# 1_Motor.net
KiCad netlist of a schematic drawn in EAGLE
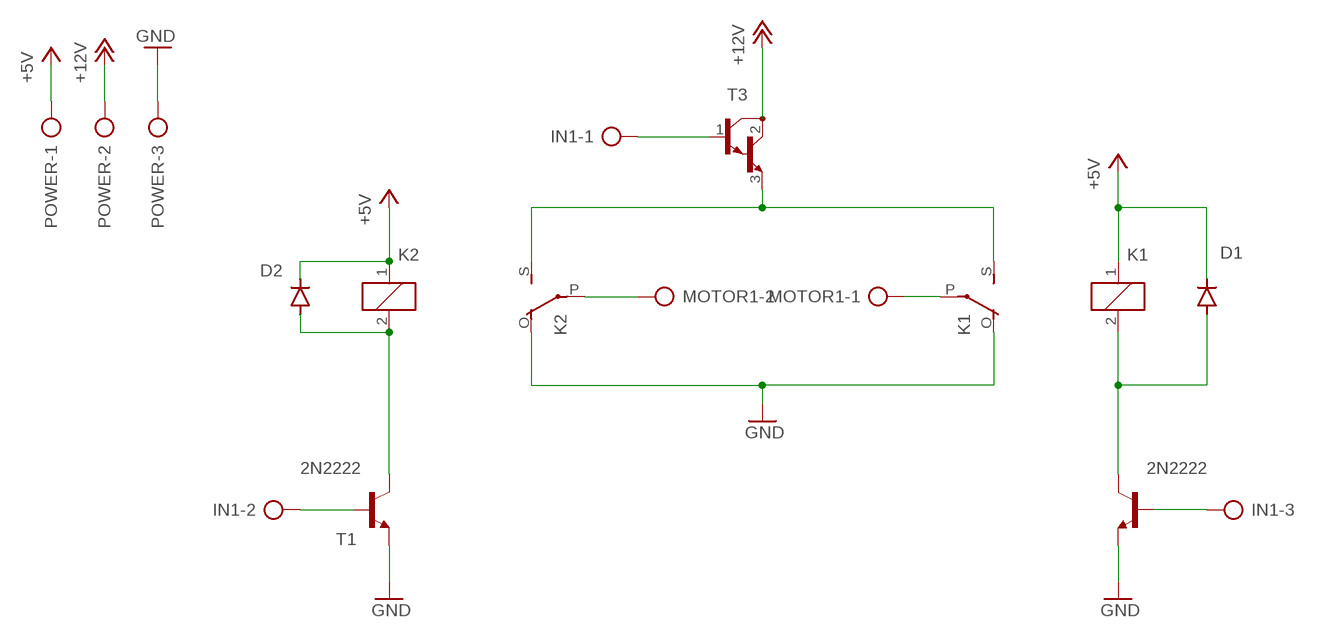
[diagram p0: schematic, sheet 1]

(export (version "E")
  (design (tool "Eeschema 10.0.6"))
  (components
    (comp (ref "D1")
      (value "1N4004")
      (footprint "eagle-import:DO41-10")
      (libsource (lib "eagle-import") (part "1N4004"))
    )
    (comp (ref "D2")
      (value "1N4004")
      (footprint "eagle-import:DO41-10")
      (libsource (lib "eagle-import") (part "1N4004"))
    )
    (comp (ref "IN1")
      (value "AK300/3")
      (footprint "eagle-import:AK300_3")
      (libsource (lib "eagle-import") (part "AK300/3"))
    )
    (comp (ref "K1")
      (value "ZF112")
      (footprint "eagle-import:ZF112")
      (libsource (lib "eagle-import") (part "ZF112"))
    )
    (comp (ref "K2")
      (value "ZF112")
      (footprint "eagle-import:ZF112")
      (libsource (lib "eagle-import") (part "ZF112"))
    )
    (comp (ref "MOTOR1")
      (value "AK300/2")
      (footprint "eagle-import:AK300_2")
      (libsource (lib "eagle-import") (part "AK300/2"))
    )
    (comp (ref "POWER")
      (value "AK300/3")
      (footprint "eagle-import:AK300_3")
      (libsource (lib "eagle-import") (part "AK300/3"))
    )
    (comp (ref "T1")
      (value "2N2222")
      (footprint "eagle-import:TO92-EBC")
      (libsource (lib "eagle-import") (part "-NPN-TO92-EBC2N2222"))
    )
    (comp (ref "T2")
      (value "2N2222")
      (footprint "eagle-import:TO92-EBC")
      (libsource (lib "eagle-import") (part "-NPN-TO92-EBC2N2222"))
    )
    (comp (ref "T3")
      (value "TIP122")
      (footprint "eagle-import:TO220")
      (libsource (lib "eagle-import") (part "TIP122"))
    )
  )
  (nets
    (net (code "1") (name "+5V") (class "Default")
      (node (ref "D1") (pin "C") (pinfunction "C_C") (pintype "passive"))
      (node (ref "D2") (pin "C") (pinfunction "C_C") (pintype "passive"))
      (node (ref "K1") (pin "1") (pinfunction "1_1") (pintype "passive"))
      (node (ref "K2") (pin "1") (pinfunction "1_1") (pintype "passive"))
      (node (ref "POWER") (pin "1") (pinfunction "KL_1") (pintype "passive"))
    )
    (net (code "2") (name "+12V") (class "Default")
      (node (ref "POWER") (pin "2") (pinfunction "KL_2") (pintype "passive"))
      (node (ref "T3") (pin "2") (pinfunction "C_2") (pintype "passive"))
    )
    (net (code "3") (name "GND") (class "Default")
      (node (ref "K1") (pin "O") (pinfunction "O_O") (pintype "passive"))
      (node (ref "K2") (pin "O") (pinfunction "O_O") (pintype "passive"))
      (node (ref "POWER") (pin "3") (pinfunction "KL_3") (pintype "passive"))
      (node (ref "T1") (pin "E") (pinfunction "E_E") (pintype "passive"))
      (node (ref "T2") (pin "E") (pinfunction "E_E") (pintype "passive"))
    )
    (net (code "4") (name "Net-(D1-PadA)") (class "Default")
      (node (ref "D1") (pin "A") (pinfunction "A_A") (pintype "passive"))
      (node (ref "K1") (pin "2") (pinfunction "2_2") (pintype "passive"))
      (node (ref "T2") (pin "C") (pinfunction "C_C") (pintype "passive"))
    )
    (net (code "5") (name "Net-(D2-PadA)") (class "Default")
      (node (ref "D2") (pin "A") (pinfunction "A_A") (pintype "passive"))
      (node (ref "K2") (pin "2") (pinfunction "2_2") (pintype "passive"))
      (node (ref "T1") (pin "C") (pinfunction "C_C") (pintype "passive"))
    )
    (net (code "6") (name "Net-(IN1A-KL)") (class "Default")
      (node (ref "IN1") (pin "1") (pinfunction "KL_1") (pintype "passive"))
      (node (ref "T3") (pin "1") (pinfunction "B_1") (pintype "passive"))
    )
    (net (code "7") (name "Net-(IN1B-KL)") (class "Default")
      (node (ref "IN1") (pin "2") (pinfunction "KL_2") (pintype "passive"))
      (node (ref "T1") (pin "B") (pinfunction "B_B") (pintype "passive"))
    )
    (net (code "8") (name "Net-(IN1C-KL)") (class "Default")
      (node (ref "IN1") (pin "3") (pinfunction "KL_3") (pintype "passive"))
      (node (ref "T2") (pin "B") (pinfunction "B_B") (pintype "passive"))
    )
    (net (code "9") (name "Net-(MOTOR1A-KL)") (class "Default")
      (node (ref "K1") (pin "P") (pinfunction "P_P") (pintype "passive"))
      (node (ref "MOTOR1") (pin "1") (pinfunction "KL_1") (pintype "passive"))
    )
    (net (code "10") (name "Net-(MOTOR1B-KL)") (class "Default")
      (node (ref "K2") (pin "P") (pinfunction "P_P") (pintype "passive"))
      (node (ref "MOTOR1") (pin "2") (pinfunction "KL_2") (pintype "passive"))
    )
    (net (code "11") (name "Net-(T3-E)") (class "Default")
      (node (ref "K1") (pin "S") (pinfunction "S_S") (pintype "passive"))
      (node (ref "K2") (pin "S") (pinfunction "S_S") (pintype "passive"))
      (node (ref "T3") (pin "3") (pinfunction "E_3") (pintype "passive"))
    )
  )
)
